# 4_-RF.net
KiCad netlist of a schematic drawn in Altium Designer
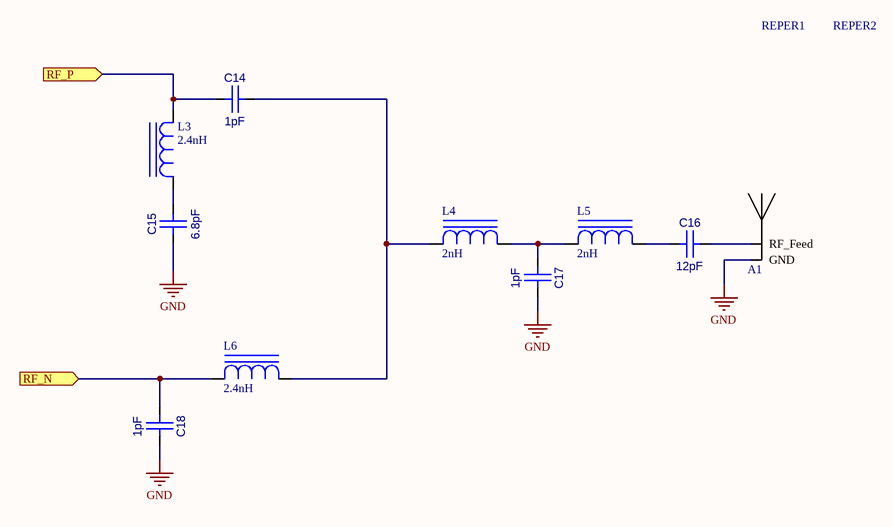
[diagram p0: [4]-RF.SchDoc]

(export (version "E")
  (design (tool "Eeschema 10.0.6"))
  (components
    (comp (ref "A1")
      (value "Antenna Wi-Fi")
      (footprint "Antenna_WiFi")
      (description "2.43GHz")
      (libsource (lib "fizik_lib") (part "Antenna Wi-Fi"))
    )
    (comp (ref "C14")
      (value "1pF")
      (footprint "CC0603")
      (description "CC0603")
      (libsource (lib "gprs_modem_2") (part "CC0603"))
    )
    (comp (ref "C15")
      (value "6.8pF")
      (footprint "CC0603")
      (description "CC0603")
      (libsource (lib "gprs_modem_2") (part "CC0603"))
    )
    (comp (ref "C16")
      (value "12pF")
      (footprint "CC0603")
      (description "CC0603")
      (libsource (lib "gprs_modem_2") (part "CC0603"))
    )
    (comp (ref "C17")
      (value "1pF")
      (footprint "CC0603")
      (description "CC0603")
      (libsource (lib "gprs_modem_2") (part "CC0603"))
    )
    (comp (ref "C18")
      (value "1pF")
      (footprint "CC0603")
      (description "CC0603")
      (libsource (lib "gprs_modem_2") (part "CC0603"))
    )
    (comp (ref "L3")
      (value "2.4nH")
      (footprint "L0402")
      (description "L0402")
      (libsource (lib "gprs_modem_2") (part "L0402"))
    )
    (comp (ref "L4")
      (value "2nH")
      (footprint "L0402")
      (description "L0402")
      (libsource (lib "gprs_modem_2") (part "L0402"))
    )
    (comp (ref "L5")
      (value "2nH")
      (footprint "L0402")
      (description "L0402")
      (libsource (lib "gprs_modem_2") (part "L0402"))
    )
    (comp (ref "L6")
      (value "2.4nH")
      (footprint "L0402")
      (description "L0402")
      (libsource (lib "gprs_modem_2") (part "L0402"))
    )
    (comp (ref "REPER1")
      (value "REPER1.2")
      (footprint "REPER1.2")
      (libsource (lib "gprs_modem_2") (part "REPER1.2"))
    )
    (comp (ref "REPER2")
      (value "REPER1.2")
      (footprint "REPER1.2")
      (libsource (lib "gprs_modem_2") (part "REPER1.2"))
    )
  )
  (nets
    (net (code "1") (name "/RF_N") (class "Default")
      (node (ref "C18") (pin "1") (pinfunction "A_1") (pintype "passive"))
      (node (ref "L6") (pin "1") (pinfunction "A_1") (pintype "passive"))
    )
    (net (code "2") (name "/RF_P") (class "Default")
      (node (ref "C14") (pin "1") (pinfunction "A_1") (pintype "passive"))
      (node (ref "L3") (pin "2") (pinfunction "C_2") (pintype "passive"))
    )
    (net (code "3") (name "GND") (class "Default")
      (node (ref "A1") (pin "2") (pinfunction "GND_2") (pintype "passive"))
      (node (ref "C15") (pin "1") (pinfunction "A_1") (pintype "passive"))
      (node (ref "C17") (pin "2") (pinfunction "B_2") (pintype "passive"))
      (node (ref "C18") (pin "2") (pinfunction "B_2") (pintype "passive"))
    )
    (net (code "4") (name "Net-(A1-RF_Feed)") (class "Default")
      (node (ref "A1") (pin "1") (pinfunction "RF_Feed_1") (pintype "passive"))
      (node (ref "C16") (pin "2") (pinfunction "B_2") (pintype "passive"))
    )
    (net (code "5") (name "Net-(C14-B)") (class "Default")
      (node (ref "C14") (pin "2") (pinfunction "B_2") (pintype "passive"))
      (node (ref "L4") (pin "1") (pinfunction "A_1") (pintype "passive"))
      (node (ref "L6") (pin "2") (pinfunction "C_2") (pintype "passive"))
    )
    (net (code "6") (name "Net-(C15-B)") (class "Default")
      (node (ref "C15") (pin "2") (pinfunction "B_2") (pintype "passive"))
      (node (ref "L3") (pin "1") (pinfunction "A_1") (pintype "passive"))
    )
    (net (code "7") (name "Net-(C16-A)") (class "Default")
      (node (ref "C16") (pin "1") (pinfunction "A_1") (pintype "passive"))
      (node (ref "L5") (pin "2") (pinfunction "C_2") (pintype "passive"))
    )
    (net (code "8") (name "Net-(C17-A)") (class "Default")
      (node (ref "C17") (pin "1") (pinfunction "A_1") (pintype "passive"))
      (node (ref "L4") (pin "2") (pinfunction "C_2") (pintype "passive"))
      (node (ref "L5") (pin "1") (pinfunction "A_1") (pintype "passive"))
    )
    (net (code "9") (name "unconnected-(REPER1-Pad1)") (class "Default")
      (node (ref "REPER1") (pin "1") (pintype "passive"))
    )
    (net (code "10") (name "unconnected-(REPER2-Pad1)") (class "Default")
      (node (ref "REPER2") (pin "1") (pintype "passive"))
    )
  )
)
